# Motor_Driver1.net
KiCad netlist of a schematic drawn in Altium Designer
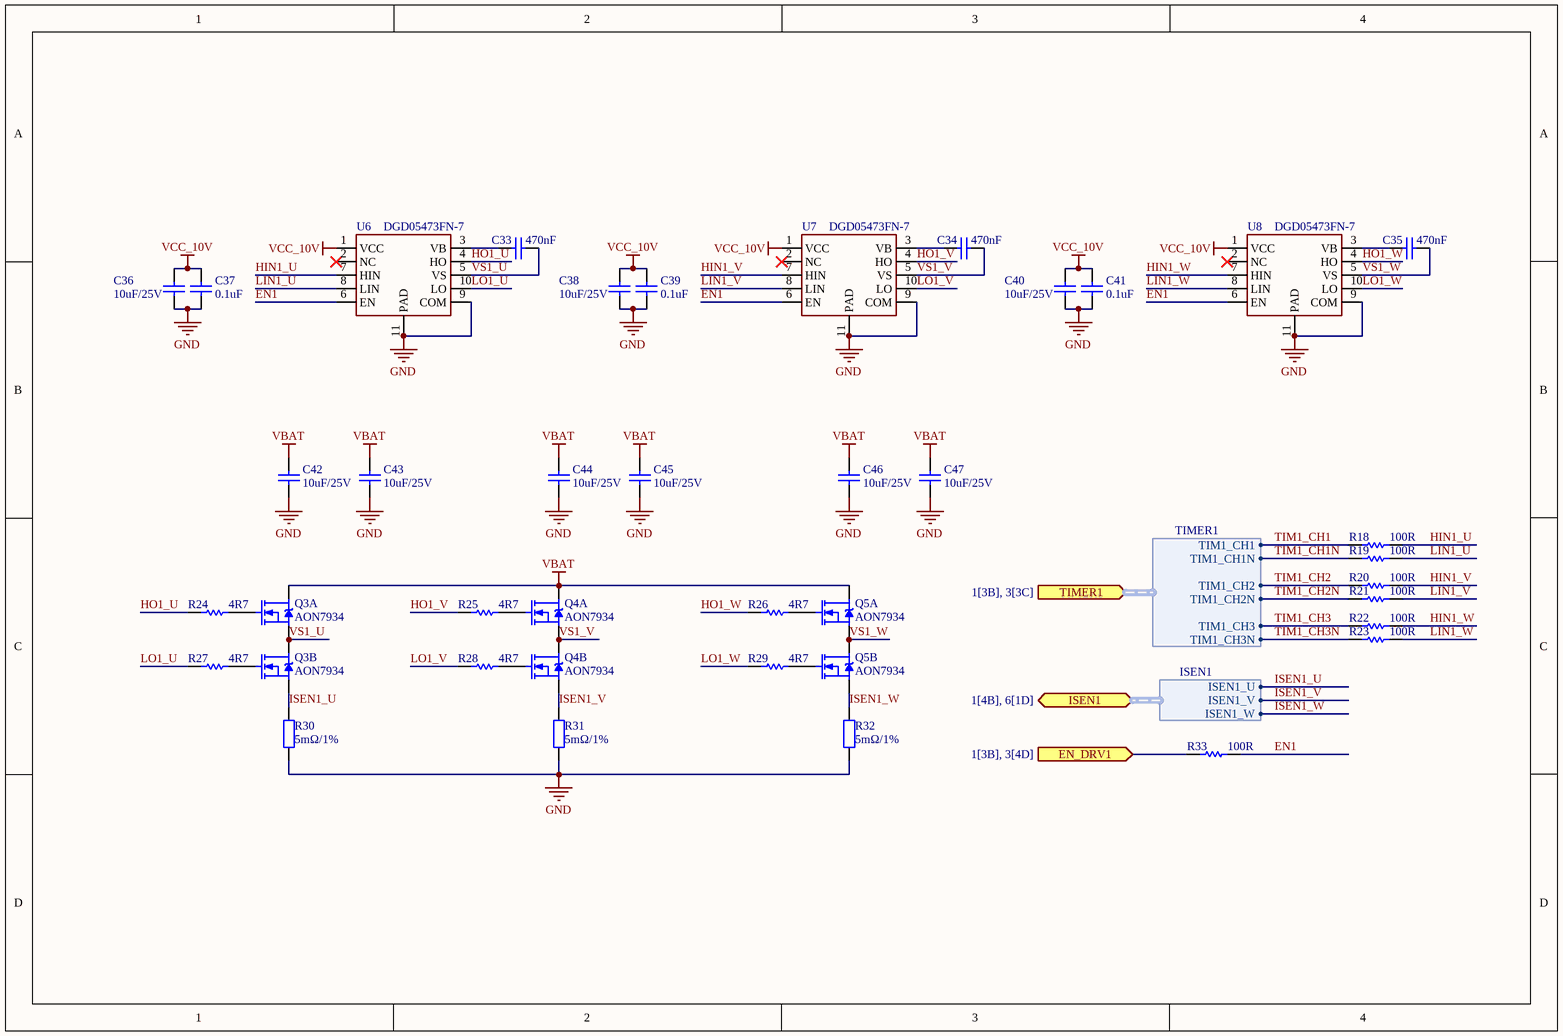
[diagram p0: Motor_Driver1.SchDoc]

(export (version "E")
  (design (tool "Eeschema 10.0.6"))
  (components
    (comp (ref "C33")
      (value "470nF")
      (footprint "C0603_NS")
      (description "Capacitor")
      (fields (field (name "PUBLISHER") "Altium Limited"))
      (libsource (lib "Miscellaneous Devices") (part "Cap"))
    )
    (comp (ref "C34")
      (value "470nF")
      (footprint "C0603_NS")
      (description "Capacitor")
      (fields (field (name "PUBLISHER") "Altium Limited"))
      (libsource (lib "Miscellaneous Devices") (part "Cap"))
    )
    (comp (ref "C35")
      (value "470nF")
      (footprint "C0603_NS")
      (description "Capacitor")
      (fields (field (name "PUBLISHER") "Altium Limited"))
      (libsource (lib "Miscellaneous Devices") (part "Cap"))
    )
    (comp (ref "C36")
      (value "10uF/25V")
      (footprint "C0603_NS")
      (description "Capacitor")
      (fields (field (name "PUBLISHER") "Altium Limited"))
      (libsource (lib "Miscellaneous Devices") (part "Cap"))
    )
    (comp (ref "C37")
      (value "0.1uF")
      (footprint "C0603_NS")
      (description "Capacitor")
      (fields (field (name "PUBLISHER") "Altium Limited"))
      (libsource (lib "Miscellaneous Devices") (part "Cap"))
    )
    (comp (ref "C38")
      (value "10uF/25V")
      (footprint "C0603_NS")
      (description "Capacitor")
      (fields (field (name "PUBLISHER") "Altium Limited"))
      (libsource (lib "Miscellaneous Devices") (part "Cap"))
    )
    (comp (ref "C39")
      (value "0.1uF")
      (footprint "C0603_NS")
      (description "Capacitor")
      (fields (field (name "PUBLISHER") "Altium Limited"))
      (libsource (lib "Miscellaneous Devices") (part "Cap"))
    )
    (comp (ref "C40")
      (value "10uF/25V")
      (footprint "C0603_NS")
      (description "Capacitor")
      (fields (field (name "PUBLISHER") "Altium Limited"))
      (libsource (lib "Miscellaneous Devices") (part "Cap"))
    )
    (comp (ref "C41")
      (value "0.1uF")
      (footprint "C0603_NS")
      (description "Capacitor")
      (fields (field (name "PUBLISHER") "Altium Limited"))
      (libsource (lib "Miscellaneous Devices") (part "Cap"))
    )
    (comp (ref "C42")
      (value "10uF/25V")
      (footprint "C0603_NS")
      (description "Capacitor")
      (libsource (lib "Miscellaneous Devices") (part "Cap"))
    )
    (comp (ref "C43")
      (value "10uF/25V")
      (footprint "C0603_NS")
      (description "Capacitor")
      (libsource (lib "Miscellaneous Devices") (part "Cap"))
    )
    (comp (ref "C44")
      (value "10uF/25V")
      (footprint "C0603_NS")
      (description "Capacitor")
      (libsource (lib "Miscellaneous Devices") (part "Cap"))
    )
    (comp (ref "C45")
      (value "10uF/25V")
      (footprint "C0603_NS")
      (description "Capacitor")
      (libsource (lib "Miscellaneous Devices") (part "Cap"))
    )
    (comp (ref "C46")
      (value "10uF/25V")
      (footprint "C0603_NS")
      (description "Capacitor")
      (libsource (lib "Miscellaneous Devices") (part "Cap"))
    )
    (comp (ref "C47")
      (value "10uF/25V")
      (footprint "C0603_NS")
      (description "Capacitor")
      (libsource (lib "Miscellaneous Devices") (part "Cap"))
    )
    (comp (ref "Q3")
      (value "AON7934")
      (footprint "POWERPAIR_3X3")
      (libsource (lib "my_library") (part "AON7934"))
    )
    (comp (ref "Q4")
      (value "AON7934")
      (footprint "POWERPAIR_3X3")
      (libsource (lib "my_library") (part "AON7934"))
    )
    (comp (ref "Q5")
      (value "AON7934")
      (footprint "POWERPAIR_3X3")
      (libsource (lib "my_library") (part "AON7934"))
    )
    (comp (ref "R18")
      (value "100R")
      (footprint "R0603_NS")
      (description "Resistor")
      (libsource (lib "Miscellaneous Devices") (part "Res1"))
    )
    (comp (ref "R19")
      (value "100R")
      (footprint "R0603_NS")
      (description "Resistor")
      (libsource (lib "Miscellaneous Devices") (part "Res1"))
    )
    (comp (ref "R20")
      (value "100R")
      (footprint "R0603_NS")
      (description "Resistor")
      (libsource (lib "Miscellaneous Devices") (part "Res1"))
    )
    (comp (ref "R21")
      (value "100R")
      (footprint "R0603_NS")
      (description "Resistor")
      (libsource (lib "Miscellaneous Devices") (part "Res1"))
    )
    (comp (ref "R22")
      (value "100R")
      (footprint "R0603_NS")
      (description "Resistor")
      (libsource (lib "Miscellaneous Devices") (part "Res1"))
    )
    (comp (ref "R23")
      (value "100R")
      (footprint "R0603_NS")
      (description "Resistor")
      (libsource (lib "Miscellaneous Devices") (part "Res1"))
    )
    (comp (ref "R24")
      (value "4R7")
      (footprint "R0603_NS")
      (description "Resistor")
      (libsource (lib "Miscellaneous Devices") (part "Res1"))
    )
    (comp (ref "R25")
      (value "4R7")
      (footprint "R0603_NS")
      (description "Resistor")
      (libsource (lib "Miscellaneous Devices") (part "Res1"))
    )
    (comp (ref "R26")
      (value "4R7")
      (footprint "R0603_NS")
      (description "Resistor")
      (libsource (lib "Miscellaneous Devices") (part "Res1"))
    )
    (comp (ref "R27")
      (value "4R7")
      (footprint "R0603_NS")
      (description "Resistor")
      (libsource (lib "Miscellaneous Devices") (part "Res1"))
    )
    (comp (ref "R28")
      (value "4R7")
      (footprint "R0603_NS")
      (description "Resistor")
      (libsource (lib "Miscellaneous Devices") (part "Res1"))
    )
    (comp (ref "R29")
      (value "4R7")
      (footprint "R0603_NS")
      (description "Resistor")
      (libsource (lib "Miscellaneous Devices") (part "Res1"))
    )
    (comp (ref "R30")
      (value "5mΩ/1%")
      (footprint "R1206_NS")
      (description "Resistor")
      (fields (field (name "PUBLISHER") "Altium Limited"))
      (libsource (lib "Miscellaneous Devices") (part "Res2"))
    )
    (comp (ref "R31")
      (value "5mΩ/1%")
      (footprint "R1206_NS")
      (description "Resistor")
      (fields (field (name "PUBLISHER") "Altium Limited"))
      (libsource (lib "Miscellaneous Devices") (part "Res2"))
    )
    (comp (ref "R32")
      (value "5mΩ/1%")
      (footprint "R1206_NS")
      (description "Resistor")
      (fields (field (name "PUBLISHER") "Altium Limited"))
      (libsource (lib "Miscellaneous Devices") (part "Res2"))
    )
    (comp (ref "R33")
      (value "100R")
      (footprint "R0603_NS")
      (description "Resistor")
      (libsource (lib "Miscellaneous Devices") (part "Res1"))
    )
    (comp (ref "U6")
      (value "DGD05473FN-7")
      (footprint "W-DFN3030-10_DGD05473")
      (libsource (lib "my_library") (part "DGD05473"))
    )
    (comp (ref "U7")
      (value "DGD05473FN-7")
      (footprint "W-DFN3030-10_DGD05473")
      (libsource (lib "my_library") (part "DGD05473"))
    )
    (comp (ref "U8")
      (value "DGD05473FN-7")
      (footprint "W-DFN3030-10_DGD05473")
      (libsource (lib "my_library") (part "DGD05473"))
    )
  )
  (nets
    (net (code "3") (name "/EN1") (class "Default")
      (node (ref "R33") (pin "2") (pinfunction "2_2") (pintype "passive"))
      (node (ref "U6") (pin "6") (pinfunction "EN_6") (pintype "passive"))
      (node (ref "U7") (pin "6") (pinfunction "EN_6") (pintype "passive"))
      (node (ref "U8") (pin "6") (pinfunction "EN_6") (pintype "passive"))
    )
    (net (code "4") (name "/EN_DRV1") (class "Default")
      (node (ref "R33") (pin "1") (pinfunction "1_1") (pintype "passive"))
    )
    (net (code "5") (name "/HIN1_U") (class "Default")
      (node (ref "R18") (pin "2") (pinfunction "2_2") (pintype "passive"))
      (node (ref "U6") (pin "7") (pinfunction "HIN_7") (pintype "passive"))
    )
    (net (code "6") (name "/HIN1_V") (class "Default")
      (node (ref "R20") (pin "2") (pinfunction "2_2") (pintype "passive"))
      (node (ref "U7") (pin "7") (pinfunction "HIN_7") (pintype "passive"))
    )
    (net (code "7") (name "/HIN1_W") (class "Default")
      (node (ref "R22") (pin "2") (pinfunction "2_2") (pintype "passive"))
      (node (ref "U8") (pin "7") (pinfunction "HIN_7") (pintype "passive"))
    )
    (net (code "8") (name "/HO1_U") (class "Default")
      (node (ref "R24") (pin "1") (pinfunction "1_1") (pintype "passive"))
      (node (ref "U6") (pin "4") (pinfunction "HO_4") (pintype "passive"))
    )
    (net (code "9") (name "/HO1_V") (class "Default")
      (node (ref "R25") (pin "1") (pinfunction "1_1") (pintype "passive"))
      (node (ref "U7") (pin "4") (pinfunction "HO_4") (pintype "passive"))
    )
    (net (code "10") (name "/HO1_W") (class "Default")
      (node (ref "R26") (pin "1") (pinfunction "1_1") (pintype "passive"))
      (node (ref "U8") (pin "4") (pinfunction "HO_4") (pintype "passive"))
    )
    (net (code "11") (name "/ISEN1_U") (class "Default")
      (node (ref "Q3") (pin "S2") (pinfunction "S2_S2") (pintype "passive"))
      (node (ref "R30") (pin "2") (pinfunction "2_2") (pintype "passive"))
    )
    (net (code "12") (name "/ISEN1_V") (class "Default")
      (node (ref "Q4") (pin "S2") (pinfunction "S2_S2") (pintype "passive"))
      (node (ref "R31") (pin "2") (pinfunction "2_2") (pintype "passive"))
    )
    (net (code "13") (name "/ISEN1_W") (class "Default")
      (node (ref "Q5") (pin "S2") (pinfunction "S2_S2") (pintype "passive"))
      (node (ref "R32") (pin "2") (pinfunction "2_2") (pintype "passive"))
    )
    (net (code "14") (name "/LIN1_U") (class "Default")
      (node (ref "R19") (pin "2") (pinfunction "2_2") (pintype "passive"))
      (node (ref "U6") (pin "8") (pinfunction "LIN_8") (pintype "passive"))
    )
    (net (code "15") (name "/LIN1_V") (class "Default")
      (node (ref "R21") (pin "2") (pinfunction "2_2") (pintype "passive"))
      (node (ref "U7") (pin "8") (pinfunction "LIN_8") (pintype "passive"))
    )
    (net (code "16") (name "/LIN1_W") (class "Default")
      (node (ref "R23") (pin "2") (pinfunction "2_2") (pintype "passive"))
      (node (ref "U8") (pin "8") (pinfunction "LIN_8") (pintype "passive"))
    )
    (net (code "17") (name "/LO1_U") (class "Default")
      (node (ref "R27") (pin "1") (pinfunction "1_1") (pintype "passive"))
      (node (ref "U6") (pin "10") (pinfunction "LO_10") (pintype "passive"))
    )
    (net (code "18") (name "/LO1_V") (class "Default")
      (node (ref "R28") (pin "1") (pinfunction "1_1") (pintype "passive"))
      (node (ref "U7") (pin "10") (pinfunction "LO_10") (pintype "passive"))
    )
    (net (code "19") (name "/LO1_W") (class "Default")
      (node (ref "R29") (pin "1") (pinfunction "1_1") (pintype "passive"))
      (node (ref "U8") (pin "10") (pinfunction "LO_10") (pintype "passive"))
    )
    (net (code "20") (name "/TIM1_CH1") (class "Default")
      (node (ref "R18") (pin "1") (pinfunction "1_1") (pintype "passive"))
    )
    (net (code "21") (name "/TIM1_CH1N") (class "Default")
      (node (ref "R19") (pin "1") (pinfunction "1_1") (pintype "passive"))
    )
    (net (code "22") (name "/TIM1_CH2") (class "Default")
      (node (ref "R20") (pin "1") (pinfunction "1_1") (pintype "passive"))
    )
    (net (code "23") (name "/TIM1_CH2N") (class "Default")
      (node (ref "R21") (pin "1") (pinfunction "1_1") (pintype "passive"))
    )
    (net (code "24") (name "/TIM1_CH3") (class "Default")
      (node (ref "R22") (pin "1") (pinfunction "1_1") (pintype "passive"))
    )
    (net (code "25") (name "/TIM1_CH3N") (class "Default")
      (node (ref "R23") (pin "1") (pinfunction "1_1") (pintype "passive"))
    )
    (net (code "26") (name "/VS1_U") (class "Default")
      (node (ref "C33") (pin "2") (pinfunction "2_2") (pintype "passive"))
      (node (ref "Q3") (pin "S1/D2") (pinfunction "S1/D2_S1/D2") (pintype "passive"))
      (node (ref "U6") (pin "5") (pinfunction "VS_5") (pintype "passive"))
    )
    (net (code "27") (name "/VS1_V") (class "Default")
      (node (ref "C34") (pin "2") (pinfunction "2_2") (pintype "passive"))
      (node (ref "Q4") (pin "S1/D2") (pinfunction "S1/D2_S1/D2") (pintype "passive"))
      (node (ref "U7") (pin "5") (pinfunction "VS_5") (pintype "passive"))
    )
    (net (code "28") (name "/VS1_W") (class "Default")
      (node (ref "C35") (pin "2") (pinfunction "2_2") (pintype "passive"))
      (node (ref "Q5") (pin "S1/D2") (pinfunction "S1/D2_S1/D2") (pintype "passive"))
      (node (ref "U8") (pin "5") (pinfunction "VS_5") (pintype "passive"))
    )
    (net (code "31") (name "GND") (class "Default")
      (node (ref "C36") (pin "2") (pinfunction "2_2") (pintype "passive"))
      (node (ref "C37") (pin "2") (pinfunction "2_2") (pintype "passive"))
      (node (ref "C38") (pin "2") (pinfunction "2_2") (pintype "passive"))
      (node (ref "C39") (pin "2") (pinfunction "2_2") (pintype "passive"))
      (node (ref "C40") (pin "2") (pinfunction "2_2") (pintype "passive"))
      (node (ref "C41") (pin "2") (pinfunction "2_2") (pintype "passive"))
      (node (ref "C42") (pin "1") (pinfunction "1_1") (pintype "passive"))
      (node (ref "C43") (pin "1") (pinfunction "1_1") (pintype "passive"))
      (node (ref "C44") (pin "1") (pinfunction "1_1") (pintype "passive"))
      (node (ref "C45") (pin "1") (pinfunction "1_1") (pintype "passive"))
      (node (ref "C46") (pin "1") (pinfunction "1_1") (pintype "passive"))
      (node (ref "C47") (pin "1") (pinfunction "1_1") (pintype "passive"))
      (node (ref "R30") (pin "1") (pinfunction "1_1") (pintype "passive"))
      (node (ref "R31") (pin "1") (pinfunction "1_1") (pintype "passive"))
      (node (ref "R32") (pin "1") (pinfunction "1_1") (pintype "passive"))
      (node (ref "U6") (pin "11") (pinfunction "PAD_11") (pintype "passive"))
      (node (ref "U6") (pin "9") (pinfunction "COM_9") (pintype "passive"))
      (node (ref "U7") (pin "11") (pinfunction "PAD_11") (pintype "passive"))
      (node (ref "U7") (pin "9") (pinfunction "COM_9") (pintype "passive"))
      (node (ref "U8") (pin "11") (pinfunction "PAD_11") (pintype "passive"))
      (node (ref "U8") (pin "9") (pinfunction "COM_9") (pintype "passive"))
    )
    (net (code "32") (name "Net-(Q3-PadG1)") (class "Default")
      (node (ref "Q3") (pin "G1") (pinfunction "G1_G1") (pintype "passive"))
      (node (ref "R24") (pin "2") (pinfunction "2_2") (pintype "passive"))
    )
    (net (code "33") (name "Net-(Q3-PadG2)") (class "Default")
      (node (ref "Q3") (pin "G2") (pinfunction "G2_G2") (pintype "passive"))
      (node (ref "R27") (pin "2") (pinfunction "2_2") (pintype "passive"))
    )
    (net (code "34") (name "Net-(Q4-PadG1)") (class "Default")
      (node (ref "Q4") (pin "G1") (pinfunction "G1_G1") (pintype "passive"))
      (node (ref "R25") (pin "2") (pinfunction "2_2") (pintype "passive"))
    )
    (net (code "35") (name "Net-(Q4-PadG2)") (class "Default")
      (node (ref "Q4") (pin "G2") (pinfunction "G2_G2") (pintype "passive"))
      (node (ref "R28") (pin "2") (pinfunction "2_2") (pintype "passive"))
    )
    (net (code "36") (name "Net-(Q5-PadG1)") (class "Default")
      (node (ref "Q5") (pin "G1") (pinfunction "G1_G1") (pintype "passive"))
      (node (ref "R26") (pin "2") (pinfunction "2_2") (pintype "passive"))
    )
    (net (code "37") (name "Net-(Q5-PadG2)") (class "Default")
      (node (ref "Q5") (pin "G2") (pinfunction "G2_G2") (pintype "passive"))
      (node (ref "R29") (pin "2") (pinfunction "2_2") (pintype "passive"))
    )
    (net (code "38") (name "Net-(U6-VB)") (class "Default")
      (node (ref "C33") (pin "1") (pinfunction "1_1") (pintype "passive"))
      (node (ref "U6") (pin "3") (pinfunction "VB_3") (pintype "passive"))
    )
    (net (code "39") (name "Net-(U7-VB)") (class "Default")
      (node (ref "C34") (pin "1") (pinfunction "1_1") (pintype "passive"))
      (node (ref "U7") (pin "3") (pinfunction "VB_3") (pintype "passive"))
    )
    (net (code "40") (name "Net-(U8-VB)") (class "Default")
      (node (ref "C35") (pin "1") (pinfunction "1_1") (pintype "passive"))
      (node (ref "U8") (pin "3") (pinfunction "VB_3") (pintype "passive"))
    )
    (net (code "41") (name "VBAT") (class "Default")
      (node (ref "C42") (pin "2") (pinfunction "2_2") (pintype "passive"))
      (node (ref "C43") (pin "2") (pinfunction "2_2") (pintype "passive"))
      (node (ref "C44") (pin "2") (pinfunction "2_2") (pintype "passive"))
      (node (ref "C45") (pin "2") (pinfunction "2_2") (pintype "passive"))
      (node (ref "C46") (pin "2") (pinfunction "2_2") (pintype "passive"))
      (node (ref "C47") (pin "2") (pinfunction "2_2") (pintype "passive"))
      (node (ref "Q3") (pin "D1") (pinfunction "D1_D1") (pintype "passive"))
      (node (ref "Q4") (pin "D1") (pinfunction "D1_D1") (pintype "passive"))
      (node (ref "Q5") (pin "D1") (pinfunction "D1_D1") (pintype "passive"))
    )
    (net (code "42") (name "VCC_10V") (class "Default")
      (node (ref "C36") (pin "1") (pinfunction "1_1") (pintype "passive"))
      (node (ref "C37") (pin "1") (pinfunction "1_1") (pintype "passive"))
      (node (ref "C38") (pin "1") (pinfunction "1_1") (pintype "passive"))
      (node (ref "C39") (pin "1") (pinfunction "1_1") (pintype "passive"))
      (node (ref "C40") (pin "1") (pinfunction "1_1") (pintype "passive"))
      (node (ref "C41") (pin "1") (pinfunction "1_1") (pintype "passive"))
      (node (ref "U6") (pin "1") (pinfunction "VCC_1") (pintype "passive"))
      (node (ref "U7") (pin "1") (pinfunction "VCC_1") (pintype "passive"))
      (node (ref "U8") (pin "1") (pinfunction "VCC_1") (pintype "passive"))
    )
    (net (code "43") (name "unconnected-(U6-NC-Pad2)") (class "Default")
      (node (ref "U6") (pin "2") (pinfunction "NC_2") (pintype "passive+no_connect"))
    )
    (net (code "44") (name "unconnected-(U7-NC-Pad2)") (class "Default")
      (node (ref "U7") (pin "2") (pinfunction "NC_2") (pintype "passive+no_connect"))
    )
    (net (code "45") (name "unconnected-(U8-NC-Pad2)") (class "Default")
      (node (ref "U8") (pin "2") (pinfunction "NC_2") (pintype "passive+no_connect"))
    )
  )
)
